# 605_motor2.net
KiCad netlist of a schematic drawn in EAGLE
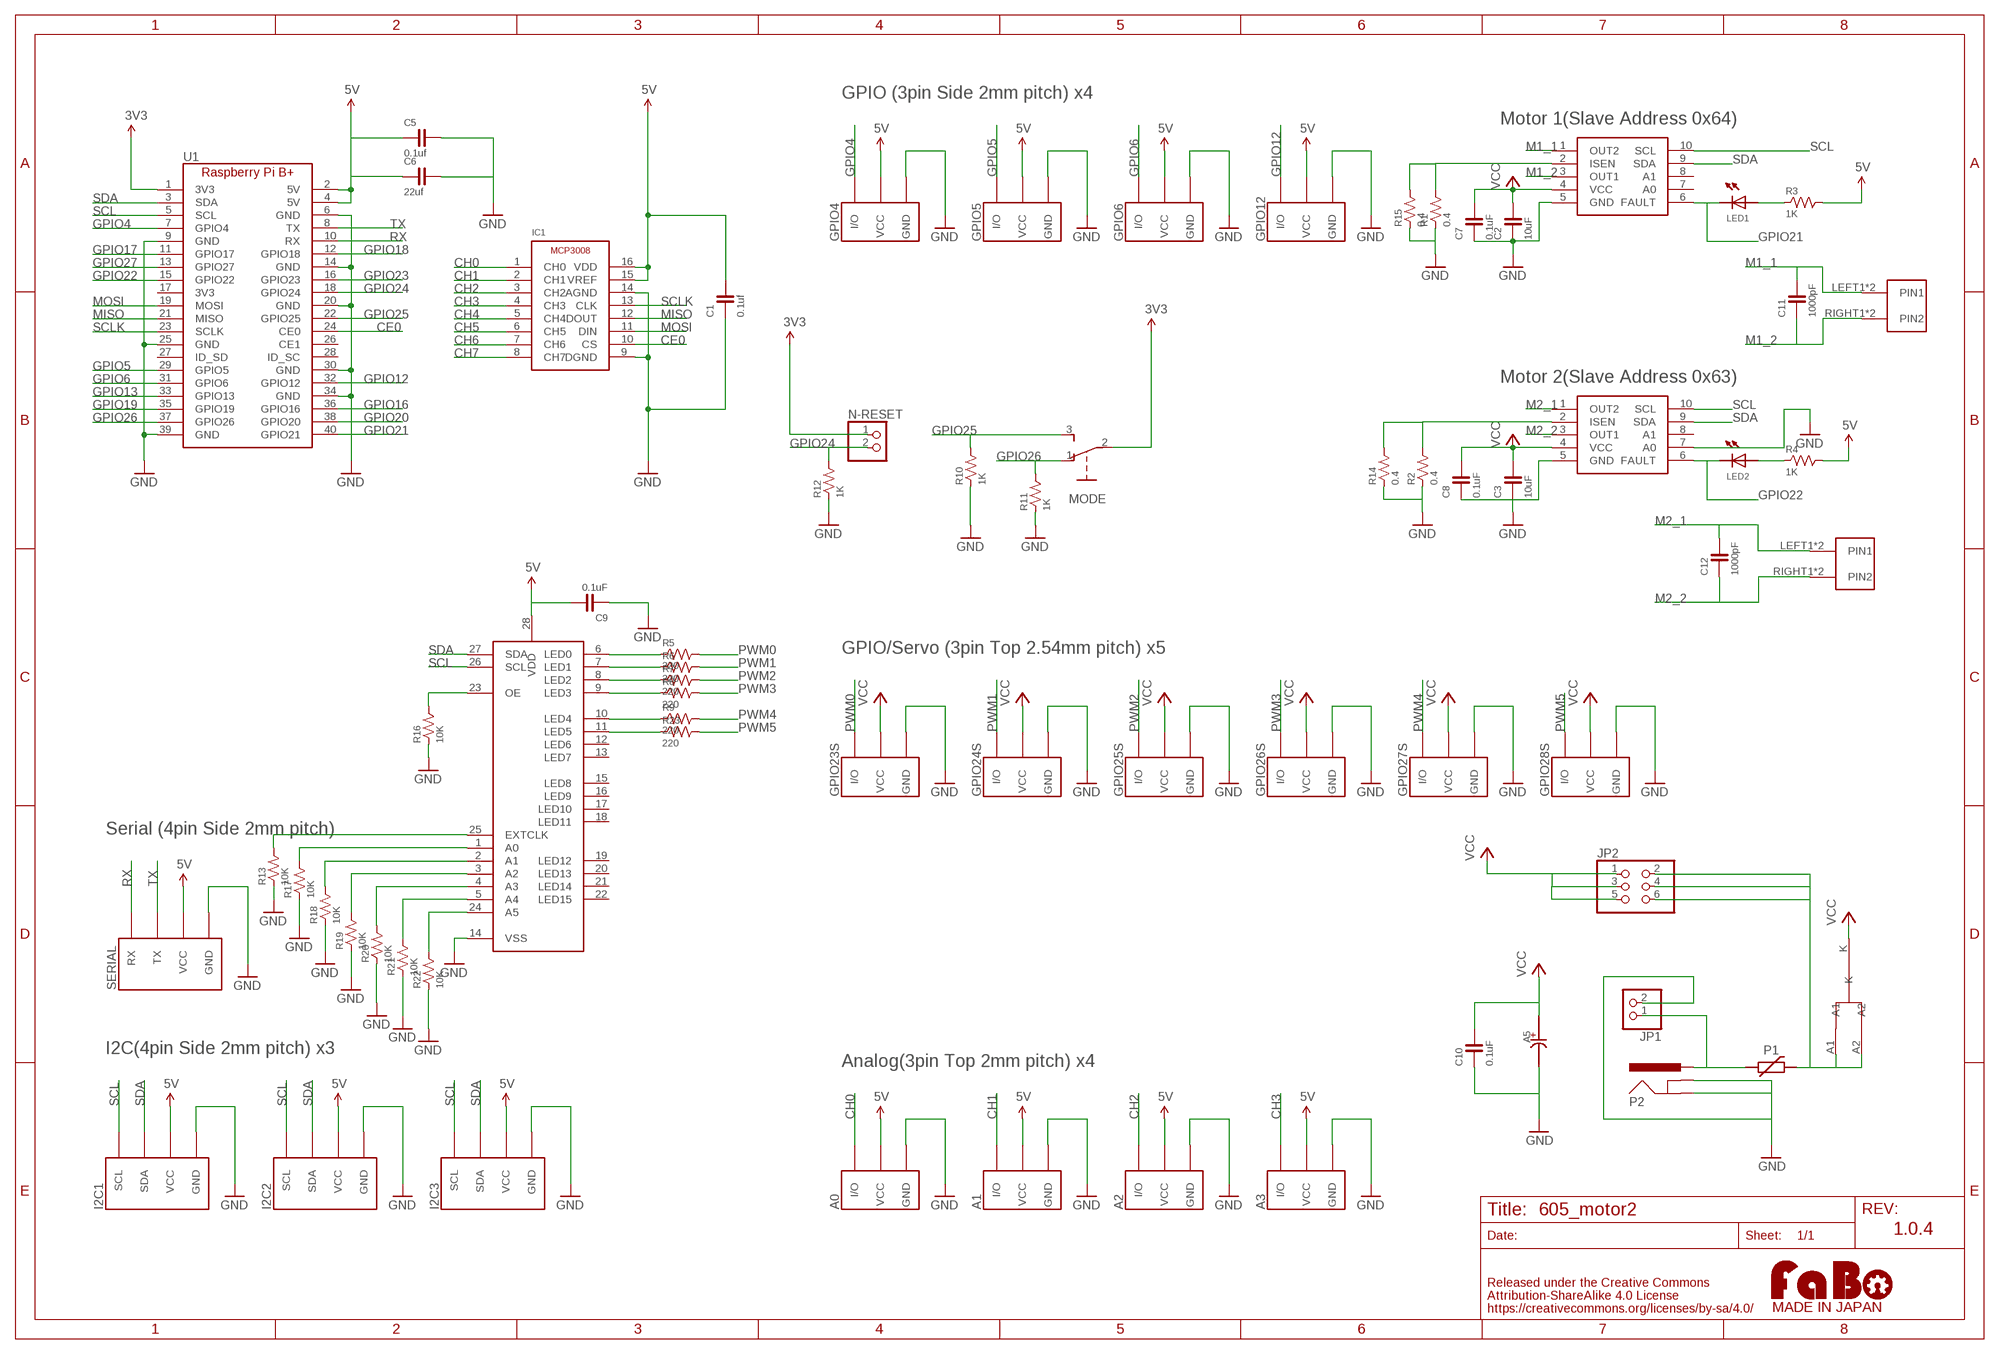
[diagram p0: schematic, sheet 1]

(export (version "E")
  (design (tool "Eeschema 10.0.6"))
  (components
    (comp (ref "A0")
      (value "FABO_BRICK_3PIN-B03B-PASK-1")
      (footprint "eagle-import:FABO_BRICK_3PIN_B03B-PASK-1")
      (libsource (lib "eagle-import") (part "FABO_BRICK_3PIN-B03B-PASK-1"))
    )
    (comp (ref "A1")
      (value "FABO_BRICK_3PIN-B03B-PASK-1")
      (footprint "eagle-import:FABO_BRICK_3PIN_B03B-PASK-1")
      (libsource (lib "eagle-import") (part "FABO_BRICK_3PIN-B03B-PASK-1"))
    )
    (comp (ref "A2")
      (value "FABO_BRICK_3PIN-B03B-PASK-1")
      (footprint "eagle-import:FABO_BRICK_3PIN_B03B-PASK-1")
      (libsource (lib "eagle-import") (part "FABO_BRICK_3PIN-B03B-PASK-1"))
    )
    (comp (ref "A3")
      (value "FABO_BRICK_3PIN-B03B-PASK-1")
      (footprint "eagle-import:FABO_BRICK_3PIN_B03B-PASK-1")
      (libsource (lib "eagle-import") (part "FABO_BRICK_3PIN-B03B-PASK-1"))
    )
    (comp (ref "A5")
      (value "CAPACITOR-ALUMIN_D12_5")
      (footprint "eagle-import:D12.5")
      (libsource (lib "eagle-import") (part "CAPACITOR-ALUMIN_D12_5"))
    )
    (comp (ref "C1")
      (value "0.1uf")
      (footprint "eagle-import:0603")
      (libsource (lib "eagle-import") (part "CAPACITOR-0603"))
    )
    (comp (ref "C2")
      (value "10uF")
      (footprint "eagle-import:0603")
      (libsource (lib "eagle-import") (part "CAPACITOR-0603"))
    )
    (comp (ref "C3")
      (value "10uF")
      (footprint "eagle-import:0603")
      (libsource (lib "eagle-import") (part "CAPACITOR-0603"))
    )
    (comp (ref "C5")
      (value "0.1uf")
      (footprint "eagle-import:0603")
      (libsource (lib "eagle-import") (part "CAPACITOR-0603"))
    )
    (comp (ref "C6")
      (value "22uf")
      (footprint "eagle-import:0603")
      (libsource (lib "eagle-import") (part "CAPACITOR-0603"))
    )
    (comp (ref "C7")
      (value "0.1uF")
      (footprint "eagle-import:0603")
      (libsource (lib "eagle-import") (part "CAPACITOR-0603"))
    )
    (comp (ref "C8")
      (value "0.1uF")
      (footprint "eagle-import:0603")
      (libsource (lib "eagle-import") (part "CAPACITOR-0603"))
    )
    (comp (ref "C9")
      (value "0.1uF")
      (footprint "eagle-import:0603")
      (libsource (lib "eagle-import") (part "CAPACITOR-0603"))
    )
    (comp (ref "C10")
      (value "0.1uF")
      (footprint "eagle-import:0603")
      (libsource (lib "eagle-import") (part "CAPACITOR-0603"))
    )
    (comp (ref "C11")
      (value "1000pF")
      (footprint "eagle-import:0603")
      (libsource (lib "eagle-import") (part "CAPACITOR-0603"))
    )
    (comp (ref "C12")
      (value "1000pF")
      (footprint "eagle-import:0603")
      (libsource (lib "eagle-import") (part "CAPACITOR-0603"))
    )
    (comp (ref "GPIO4")
      (value "FABO_BRICK_3PIN-S03B-PASK-2")
      (footprint "eagle-import:FABO_BRICK_3PIN_S03B-PASK-2")
      (libsource (lib "eagle-import") (part "FABO_BRICK_3PIN-S03B-PASK-2"))
    )
    (comp (ref "GPIO5")
      (value "FABO_BRICK_3PIN-S03B-PASK-2")
      (footprint "eagle-import:FABO_BRICK_3PIN_S03B-PASK-2")
      (libsource (lib "eagle-import") (part "FABO_BRICK_3PIN-S03B-PASK-2"))
    )
    (comp (ref "GPIO6")
      (value "FABO_BRICK_3PIN-S03B-PASK-2")
      (footprint "eagle-import:FABO_BRICK_3PIN_S03B-PASK-2")
      (libsource (lib "eagle-import") (part "FABO_BRICK_3PIN-S03B-PASK-2"))
    )
    (comp (ref "GPIO12")
      (value "FABO_BRICK_3PIN-S03B-PASK-2")
      (footprint "eagle-import:FABO_BRICK_3PIN_S03B-PASK-2")
      (libsource (lib "eagle-import") (part "FABO_BRICK_3PIN-S03B-PASK-2"))
    )
    (comp (ref "GPIO23S")
      (value "FABO_BRICK_3PIN-HEADER")
      (footprint "eagle-import:FABO_BRICK_3PIN_HEADER")
      (libsource (lib "eagle-import") (part "FABO_BRICK_3PIN-HEADER"))
    )
    (comp (ref "GPIO24S")
      (value "FABO_BRICK_3PIN-HEADER")
      (footprint "eagle-import:FABO_BRICK_3PIN_HEADER")
      (libsource (lib "eagle-import") (part "FABO_BRICK_3PIN-HEADER"))
    )
    (comp (ref "GPIO25S")
      (value "FABO_BRICK_3PIN-HEADER")
      (footprint "eagle-import:FABO_BRICK_3PIN_HEADER")
      (libsource (lib "eagle-import") (part "FABO_BRICK_3PIN-HEADER"))
    )
    (comp (ref "GPIO26S")
      (value "FABO_BRICK_3PIN-HEADER")
      (footprint "eagle-import:FABO_BRICK_3PIN_HEADER")
      (libsource (lib "eagle-import") (part "FABO_BRICK_3PIN-HEADER"))
    )
    (comp (ref "GPIO27S")
      (value "FABO_BRICK_3PIN-HEADER")
      (footprint "eagle-import:FABO_BRICK_3PIN_HEADER")
      (libsource (lib "eagle-import") (part "FABO_BRICK_3PIN-HEADER"))
    )
    (comp (ref "GPIO28S")
      (value "FABO_BRICK_3PIN-HEADER")
      (footprint "eagle-import:FABO_BRICK_3PIN_HEADER")
      (libsource (lib "eagle-import") (part "FABO_BRICK_3PIN-HEADER"))
    )
    (comp (ref "I2C1")
      (value "FABO_BRICK_I2C-S04B-PASK-2")
      (footprint "eagle-import:FABO_BRICK_I2C_S04B-PASK-2")
      (libsource (lib "eagle-import") (part "FABO_BRICK_I2C-S04B-PASK-2"))
    )
    (comp (ref "I2C2")
      (value "FABO_BRICK_I2C-S04B-PASK-2")
      (footprint "eagle-import:FABO_BRICK_I2C_S04B-PASK-2")
      (libsource (lib "eagle-import") (part "FABO_BRICK_I2C-S04B-PASK-2"))
    )
    (comp (ref "I2C3")
      (value "FABO_BRICK_I2C-S04B-PASK-2")
      (footprint "eagle-import:FABO_BRICK_I2C_S04B-PASK-2")
      (libsource (lib "eagle-import") (part "FABO_BRICK_I2C-S04B-PASK-2"))
    )
    (comp (ref "IC1")
      (value "MICROCHIP-MCP3008")
      (footprint "eagle-import:MICROCHIP-MCP3008")
      (libsource (lib "eagle-import") (part "MICROCHIP-MCP3008"))
    )
    (comp (ref "JP1")
      (value "PINHD-1X2")
      (footprint "eagle-import:1X02")
      (libsource (lib "eagle-import") (part "PINHD-1X2"))
    )
    (comp (ref "JP2")
      (value "PINHD-2X3")
      (footprint "eagle-import:2X03")
      (libsource (lib "eagle-import") (part "PINHD-2X3"))
    )
    (comp (ref "LED1")
      (value "LED-0603")
      (footprint "eagle-import:0603")
      (libsource (lib "eagle-import") (part "LED-0603"))
    )
    (comp (ref "LED2")
      (value "LED-0603")
      (footprint "eagle-import:0603")
      (libsource (lib "eagle-import") (part "LED-0603"))
    )
    (comp (ref "MODE")
      (value "SLIDE-EG1218")
      (footprint "eagle-import:EG1218")
      (libsource (lib "eagle-import") (part "SLIDE-EG1218"))
    )
    (comp (ref "N-RESET")
      (value "PINHD-1X2")
      (footprint "eagle-import:1X02")
      (libsource (lib "eagle-import") (part "PINHD-1X2"))
    )
    (comp (ref "P1")
      (value "POLYSWITCH1206")
      (footprint "eagle-import:1206")
      (libsource (lib "eagle-import") (part "POLYSWITCH1206"))
    )
    (comp (ref "P2")
      (value "DC-JACKM04339A0")
      (footprint "eagle-import:M04339A0")
      (libsource (lib "eagle-import") (part "DC-JACKM04339A0"))
    )
    (comp (ref "R1")
      (value "0.4")
      (footprint "eagle-import:0603")
      (libsource (lib "eagle-import") (part "RESISTOR-0603"))
    )
    (comp (ref "R2")
      (value "0.4")
      (footprint "eagle-import:0603")
      (libsource (lib "eagle-import") (part "RESISTOR-0603"))
    )
    (comp (ref "R3")
      (value "1K")
      (footprint "eagle-import:0603")
      (libsource (lib "eagle-import") (part "RESISTOR-0603"))
    )
    (comp (ref "R4")
      (value "1K")
      (footprint "eagle-import:0603")
      (libsource (lib "eagle-import") (part "RESISTOR-0603"))
    )
    (comp (ref "R5")
      (value "220")
      (footprint "eagle-import:0603")
      (libsource (lib "eagle-import") (part "RESISTOR-0603"))
    )
    (comp (ref "R6")
      (value "220")
      (footprint "eagle-import:0603")
      (libsource (lib "eagle-import") (part "RESISTOR-0603"))
    )
    (comp (ref "R7")
      (value "220")
      (footprint "eagle-import:0603")
      (libsource (lib "eagle-import") (part "RESISTOR-0603"))
    )
    (comp (ref "R8")
      (value "220")
      (footprint "eagle-import:0603")
      (libsource (lib "eagle-import") (part "RESISTOR-0603"))
    )
    (comp (ref "R9")
      (value "220")
      (footprint "eagle-import:0603")
      (libsource (lib "eagle-import") (part "RESISTOR-0603"))
    )
    (comp (ref "R10")
      (value "1K")
      (footprint "eagle-import:0603")
      (libsource (lib "eagle-import") (part "RESISTOR-0603"))
    )
    (comp (ref "R11")
      (value "1K")
      (footprint "eagle-import:0603")
      (libsource (lib "eagle-import") (part "RESISTOR-0603"))
    )
    (comp (ref "R12")
      (value "1K")
      (footprint "eagle-import:0603")
      (libsource (lib "eagle-import") (part "RESISTOR-0603"))
    )
    (comp (ref "R13")
      (value "10K")
      (footprint "eagle-import:0402")
      (libsource (lib "eagle-import") (part "RESISTOR-0402"))
    )
    (comp (ref "R14")
      (value "0.4")
      (footprint "eagle-import:0603")
      (libsource (lib "eagle-import") (part "RESISTOR-0603"))
    )
    (comp (ref "R15")
      (value "0.4")
      (footprint "eagle-import:0603")
      (libsource (lib "eagle-import") (part "RESISTOR-0603"))
    )
    (comp (ref "R16")
      (value "10K")
      (footprint "eagle-import:0603")
      (libsource (lib "eagle-import") (part "RESISTOR-0603"))
    )
    (comp (ref "R17")
      (value "10K")
      (footprint "eagle-import:0603")
      (libsource (lib "eagle-import") (part "RESISTOR-0603"))
    )
    (comp (ref "R18")
      (value "10K")
      (footprint "eagle-import:0603")
      (libsource (lib "eagle-import") (part "RESISTOR-0603"))
    )
    (comp (ref "R19")
      (value "10K")
      (footprint "eagle-import:0603")
      (libsource (lib "eagle-import") (part "RESISTOR-0603"))
    )
    (comp (ref "R20")
      (value "10K")
      (footprint "eagle-import:0603")
      (libsource (lib "eagle-import") (part "RESISTOR-0603"))
    )
    (comp (ref "R21")
      (value "10K")
      (footprint "eagle-import:0603")
      (libsource (lib "eagle-import") (part "RESISTOR-0603"))
    )
    (comp (ref "R22")
      (value "10K")
      (footprint "eagle-import:0402")
      (libsource (lib "eagle-import") (part "RESISTOR-0402"))
    )
    (comp (ref "R23")
      (value "220")
      (footprint "eagle-import:0603")
      (libsource (lib "eagle-import") (part "RESISTOR-0603"))
    )
    (comp (ref "S1")
      (value "STPS15L30C")
      (footprint "eagle-import:STPS15L30C")
      (libsource (lib "eagle-import") (part "STPS15L30C"))
    )
    (comp (ref "SERIAL")
      (value "FABO_BRICK_SERIAL-S04B-PASK-2")
      (footprint "eagle-import:FABO_BRICK_SERIAL_S04B-PASK-2")
      (libsource (lib "eagle-import") (part "FABO_BRICK_SERIAL-S04B-PASK-2"))
    )
    (comp (ref "U$8")
      (value "DRV8830")
      (footprint "eagle-import:DRV8830")
      (libsource (lib "eagle-import") (part "DRV8830"))
    )
    (comp (ref "U$9")
      (value "PCA9685")
      (footprint "eagle-import:PCA9685")
      (libsource (lib "eagle-import") (part "PCA9685"))
    )
    (comp (ref "U$10")
      (value "DRV8830")
      (footprint "eagle-import:DRV8830")
      (libsource (lib "eagle-import") (part "DRV8830"))
    )
    (comp (ref "U$12")
      (value "ML-1400-S1")
      (footprint "eagle-import:ML-1400-S1")
      (libsource (lib "eagle-import") (part "ML-1400-S1"))
    )
    (comp (ref "U$13")
      (value "ML-1400-S1")
      (footprint "eagle-import:ML-1400-S1")
      (libsource (lib "eagle-import") (part "ML-1400-S1"))
    )
    (comp (ref "U$14")
      (value "LOGO_FABO-M")
      (footprint "eagle-import:LOGO_FABO_MS")
      (libsource (lib "eagle-import") (part "LOGO_FABO-M"))
    )
    (comp (ref "U1")
      (value "RASPBERRY_PI_B+")
      (footprint "eagle-import:RASPBERRY_PI_B+")
      (libsource (lib "eagle-import") (part "RASPBERRY_PI_B+"))
    )
  )
  (nets
    (net (code "1") (name "/CE0") (class "Default")
      (node (ref "IC1") (pin "10") (pinfunction "CS_10") (pintype "bidirectional"))
      (node (ref "U1") (pin "24") (pinfunction "CE0_24") (pintype "bidirectional"))
    )
    (net (code "2") (name "/CH0") (class "Default")
      (node (ref "A0") (pin "I/O") (pinfunction "I/O_I/O") (pintype "bidirectional"))
      (node (ref "IC1") (pin "1") (pinfunction "CH0_1") (pintype "bidirectional"))
    )
    (net (code "3") (name "/CH1") (class "Default")
      (node (ref "A1") (pin "I/O") (pinfunction "I/O_I/O") (pintype "bidirectional"))
      (node (ref "IC1") (pin "2") (pinfunction "CH1_2") (pintype "bidirectional"))
    )
    (net (code "4") (name "/CH2") (class "Default")
      (node (ref "A2") (pin "I/O") (pinfunction "I/O_I/O") (pintype "bidirectional"))
      (node (ref "IC1") (pin "3") (pinfunction "CH2_3") (pintype "bidirectional"))
    )
    (net (code "5") (name "/CH3") (class "Default")
      (node (ref "A3") (pin "I/O") (pinfunction "I/O_I/O") (pintype "bidirectional"))
      (node (ref "IC1") (pin "4") (pinfunction "CH3_4") (pintype "bidirectional"))
    )
    (net (code "6") (name "/CH4") (class "Default")
      (node (ref "IC1") (pin "5") (pinfunction "CH4_5") (pintype "bidirectional"))
    )
    (net (code "7") (name "/CH5") (class "Default")
      (node (ref "IC1") (pin "6") (pinfunction "CH5_6") (pintype "bidirectional"))
    )
    (net (code "8") (name "/CH6") (class "Default")
      (node (ref "IC1") (pin "7") (pinfunction "CH6_7") (pintype "bidirectional"))
    )
    (net (code "9") (name "/CH7") (class "Default")
      (node (ref "IC1") (pin "8") (pinfunction "CH7_8") (pintype "bidirectional"))
    )
    (net (code "10") (name "/GPIO4") (class "Default")
      (node (ref "GPIO4") (pin "I/O") (pinfunction "I/O_I/O") (pintype "bidirectional"))
      (node (ref "U1") (pin "7") (pinfunction "GPIO4_7") (pintype "bidirectional"))
    )
    (net (code "11") (name "/GPIO5") (class "Default")
      (node (ref "GPIO5") (pin "I/O") (pinfunction "I/O_I/O") (pintype "bidirectional"))
      (node (ref "U1") (pin "29") (pinfunction "GPIO5_29") (pintype "bidirectional"))
    )
    (net (code "12") (name "/GPIO6") (class "Default")
      (node (ref "GPIO6") (pin "I/O") (pinfunction "I/O_I/O") (pintype "bidirectional"))
      (node (ref "U1") (pin "31") (pinfunction "GPIO6_31") (pintype "bidirectional"))
    )
    (net (code "13") (name "/GPIO12") (class "Default")
      (node (ref "GPIO12") (pin "I/O") (pinfunction "I/O_I/O") (pintype "bidirectional"))
      (node (ref "U1") (pin "32") (pinfunction "GPIO12_32") (pintype "bidirectional"))
    )
    (net (code "14") (name "/GPIO13") (class "Default")
      (node (ref "U1") (pin "33") (pinfunction "GPIO13_33") (pintype "bidirectional"))
    )
    (net (code "15") (name "/GPIO16") (class "Default")
      (node (ref "U1") (pin "36") (pinfunction "GPIO16_36") (pintype "bidirectional"))
    )
    (net (code "16") (name "/GPIO17") (class "Default")
      (node (ref "U1") (pin "11") (pinfunction "GPIO17_11") (pintype "bidirectional"))
    )
    (net (code "17") (name "/GPIO18") (class "Default")
      (node (ref "U1") (pin "12") (pinfunction "GPIO18_12") (pintype "bidirectional"))
    )
    (net (code "18") (name "/GPIO19") (class "Default")
      (node (ref "U1") (pin "35") (pinfunction "GPIO19_35") (pintype "bidirectional"))
    )
    (net (code "19") (name "/GPIO20") (class "Default")
      (node (ref "U1") (pin "38") (pinfunction "GPIO20_38") (pintype "bidirectional"))
    )
    (net (code "20") (name "/GPIO21") (class "Default")
      (node (ref "LED1") (pin "CATHODE") (pinfunction "CATHODE_CATHODE") (pintype "passive"))
      (node (ref "U$8") (pin "6") (pinfunction "FAULT_6") (pintype "bidirectional"))
      (node (ref "U1") (pin "40") (pinfunction "GPIO21_40") (pintype "bidirectional"))
    )
    (net (code "21") (name "/GPIO22") (class "Default")
      (node (ref "LED2") (pin "CATHODE") (pinfunction "CATHODE_CATHODE") (pintype "passive"))
      (node (ref "U$10") (pin "6") (pinfunction "FAULT_6") (pintype "bidirectional"))
      (node (ref "U1") (pin "15") (pinfunction "GPIO22_15") (pintype "bidirectional"))
    )
    (net (code "22") (name "/GPIO23") (class "Default")
      (node (ref "U1") (pin "16") (pinfunction "GPIO23_16") (pintype "bidirectional"))
    )
    (net (code "23") (name "/GPIO24") (class "Default")
      (node (ref "N-RESET") (pin "2") (pinfunction "2_2") (pintype "passive"))
      (node (ref "R12") (pin "2") (pinfunction "2_2") (pintype "bidirectional"))
      (node (ref "U1") (pin "18") (pinfunction "GPIO24_18") (pintype "bidirectional"))
    )
    (net (code "24") (name "/GPIO25") (class "Default")
      (node (ref "MODE") (pin "3") (pinfunction "3_3") (pintype "passive"))
      (node (ref "R10") (pin "2") (pinfunction "2_2") (pintype "bidirectional"))
      (node (ref "U1") (pin "22") (pinfunction "GPIO25_22") (pintype "bidirectional"))
    )
    (net (code "25") (name "/GPIO26") (class "Default")
      (node (ref "MODE") (pin "1") (pinfunction "1_1") (pintype "passive"))
      (node (ref "R11") (pin "2") (pinfunction "2_2") (pintype "bidirectional"))
      (node (ref "U1") (pin "37") (pinfunction "GPIO26_37") (pintype "bidirectional"))
    )
    (net (code "26") (name "/GPIO27") (class "Default")
      (node (ref "U1") (pin "13") (pinfunction "GPIO27_13") (pintype "bidirectional"))
    )
    (net (code "27") (name "/M1_1") (class "Default")
      (node (ref "C11") (pin "2") (pinfunction "2_2") (pintype "passive"))
      (node (ref "U$12") (pin "LEFT1") (pinfunction "PIN1_LEFT1") (pintype "bidirectional"))
      (node (ref "U$12") (pin "LEFT2") (pinfunction "PIN1_LEFT2") (pintype "bidirectional"))
      (node (ref "U$8") (pin "1") (pinfunction "OUT2_1") (pintype "bidirectional"))
    )
    (net (code "28") (name "/M1_2") (class "Default")
      (node (ref "C11") (pin "1") (pinfunction "1_1") (pintype "passive"))
      (node (ref "U$12") (pin "RIGHT1") (pinfunction "PIN2_RIGHT1") (pintype "bidirectional"))
      (node (ref "U$12") (pin "RIGHT2") (pinfunction "PIN2_RIGHT2") (pintype "bidirectional"))
      (node (ref "U$8") (pin "3") (pinfunction "OUT1_3") (pintype "bidirectional"))
    )
    (net (code "29") (name "/M2_1") (class "Default")
      (node (ref "C12") (pin "2") (pinfunction "2_2") (pintype "passive"))
      (node (ref "U$10") (pin "1") (pinfunction "OUT2_1") (pintype "bidirectional"))
      (node (ref "U$13") (pin "LEFT1") (pinfunction "PIN1_LEFT1") (pintype "bidirectional"))
      (node (ref "U$13") (pin "LEFT2") (pinfunction "PIN1_LEFT2") (pintype "bidirectional"))
    )
    (net (code "30") (name "/M2_2") (class "Default")
      (node (ref "C12") (pin "1") (pinfunction "1_1") (pintype "passive"))
      (node (ref "U$10") (pin "3") (pinfunction "OUT1_3") (pintype "bidirectional"))
      (node (ref "U$13") (pin "RIGHT1") (pinfunction "PIN2_RIGHT1") (pintype "bidirectional"))
      (node (ref "U$13") (pin "RIGHT2") (pinfunction "PIN2_RIGHT2") (pintype "bidirectional"))
    )
    (net (code "31") (name "/MISO") (class "Default")
      (node (ref "IC1") (pin "12") (pinfunction "DOUT_12") (pintype "bidirectional"))
      (node (ref "U1") (pin "21") (pinfunction "MISO_21") (pintype "bidirectional"))
    )
    (net (code "32") (name "/MOSI") (class "Default")
      (node (ref "IC1") (pin "11") (pinfunction "DIN_11") (pintype "bidirectional"))
      (node (ref "U1") (pin "19") (pinfunction "MOSI_19") (pintype "bidirectional"))
    )
    (net (code "33") (name "/PWM0") (class "Default")
      (node (ref "GPIO23S") (pin "I/O") (pinfunction "I/O_I/O") (pintype "bidirectional"))
      (node (ref "R5") (pin "2") (pinfunction "2_2") (pintype "bidirectional"))
    )
    (net (code "34") (name "/PWM1") (class "Default")
      (node (ref "GPIO24S") (pin "I/O") (pinfunction "I/O_I/O") (pintype "bidirectional"))
      (node (ref "R6") (pin "2") (pinfunction "2_2") (pintype "bidirectional"))
    )
    (net (code "35") (name "/PWM2") (class "Default")
      (node (ref "GPIO25S") (pin "I/O") (pinfunction "I/O_I/O") (pintype "bidirectional"))
      (node (ref "R7") (pin "2") (pinfunction "2_2") (pintype "bidirectional"))
    )
    (net (code "36") (name "/PWM3") (class "Default")
      (node (ref "GPIO26S") (pin "I/O") (pinfunction "I/O_I/O") (pintype "bidirectional"))
      (node (ref "R8") (pin "2") (pinfunction "2_2") (pintype "bidirectional"))
    )
    (net (code "37") (name "/PWM4") (class "Default")
      (node (ref "GPIO27S") (pin "I/O") (pinfunction "I/O_I/O") (pintype "bidirectional"))
      (node (ref "R9") (pin "2") (pinfunction "2_2") (pintype "bidirectional"))
    )
    (net (code "38") (name "/PWM5") (class "Default")
      (node (ref "GPIO28S") (pin "I/O") (pinfunction "I/O_I/O") (pintype "bidirectional"))
      (node (ref "R23") (pin "2") (pinfunction "2_2") (pintype "bidirectional"))
    )
    (net (code "39") (name "/RX") (class "Default")
      (node (ref "SERIAL") (pin "RX") (pinfunction "RX_RX") (pintype "bidirectional"))
      (node (ref "U1") (pin "10") (pinfunction "RX_10") (pintype "bidirectional"))
    )
    (net (code "40") (name "/SCL") (class "Default")
      (node (ref "I2C1") (pin "SCL") (pinfunction "SCL_SCL") (pintype "bidirectional"))
      (node (ref "I2C2") (pin "SCL") (pinfunction "SCL_SCL") (pintype "bidirectional"))
      (node (ref "I2C3") (pin "SCL") (pinfunction "SCL_SCL") (pintype "bidirectional"))
      (node (ref "U$10") (pin "10") (pinfunction "SCL_10") (pintype "bidirectional"))
      (node (ref "U$8") (pin "10") (pinfunction "SCL_10") (pintype "bidirectional"))
      (node (ref "U$9") (pin "26") (pinfunction "SCL_26") (pintype "bidirectional"))
      (node (ref "U1") (pin "5") (pinfunction "SCL_5") (pintype "bidirectional"))
    )
    (net (code "41") (name "/SCLK") (class "Default")
      (node (ref "IC1") (pin "13") (pinfunction "CLK_13") (pintype "bidirectional"))
      (node (ref "U1") (pin "23") (pinfunction "SCLK_23") (pintype "bidirectional"))
    )
    (net (code "42") (name "/SDA") (class "Default")
      (node (ref "I2C1") (pin "SDA") (pinfunction "SDA_SDA") (pintype "bidirectional"))
      (node (ref "I2C2") (pin "SDA") (pinfunction "SDA_SDA") (pintype "bidirectional"))
      (node (ref "I2C3") (pin "SDA") (pinfunction "SDA_SDA") (pintype "bidirectional"))
      (node (ref "U$10") (pin "9") (pinfunction "SDA_9") (pintype "bidirectional"))
      (node (ref "U$8") (pin "9") (pinfunction "SDA_9") (pintype "bidirectional"))
      (node (ref "U$9") (pin "27") (pinfunction "SDA_27") (pintype "bidirectional"))
      (node (ref "U1") (pin "3") (pinfunction "SDA_3") (pintype "bidirectional"))
    )
    (net (code "43") (name "/TX") (class "Default")
      (node (ref "SERIAL") (pin "TX") (pinfunction "TX_TX") (pintype "bidirectional"))
      (node (ref "U1") (pin "8") (pinfunction "TX_8") (pintype "bidirectional"))
    )
    (net (code "44") (name "3V3") (class "Default")
      (node (ref "MODE") (pin "2") (pinfunction "2_2") (pintype "passive"))
      (node (ref "N-RESET") (pin "1") (pinfunction "1_1") (pintype "passive"))
      (node (ref "U1") (pin "1") (pinfunction "3V3_1") (pintype "bidirectional"))
    )
    (net (code "45") (name "5V") (class "Default")
      (node (ref "A0") (pin "VCC") (pinfunction "VCC_VCC") (pintype "bidirectional"))
      (node (ref "A1") (pin "VCC") (pinfunction "VCC_VCC") (pintype "bidirectional"))
      (node (ref "A2") (pin "VCC") (pinfunction "VCC_VCC") (pintype "bidirectional"))
      (node (ref "A3") (pin "VCC") (pinfunction "VCC_VCC") (pintype "bidirectional"))
      (node (ref "C1") (pin "2") (pinfunction "2_2") (pintype "passive"))
      (node (ref "C5") (pin "1") (pinfunction "1_1") (pintype "passive"))
      (node (ref "C6") (pin "1") (pinfunction "1_1") (pintype "passive"))
      (node (ref "C9") (pin "2") (pinfunction "2_2") (pintype "passive"))
      (node (ref "GPIO12") (pin "VCC") (pinfunction "VCC_VCC") (pintype "bidirectional"))
      (node (ref "GPIO4") (pin "VCC") (pinfunction "VCC_VCC") (pintype "bidirectional"))
      (node (ref "GPIO5") (pin "VCC") (pinfunction "VCC_VCC") (pintype "bidirectional"))
      (node (ref "GPIO6") (pin "VCC") (pinfunction "VCC_VCC") (pintype "bidirectional"))
      (node (ref "I2C1") (pin "VCC") (pinfunction "VCC_VCC") (pintype "bidirectional"))
      (node (ref "I2C2") (pin "VCC") (pinfunction "VCC_VCC") (pintype "bidirectional"))
      (node (ref "I2C3") (pin "VCC") (pinfunction "VCC_VCC") (pintype "bidirectional"))
      (node (ref "IC1") (pin "15") (pinfunction "VREF_15") (pintype "bidirectional"))
      (node (ref "IC1") (pin "16") (pinfunction "VDD_16") (pintype "bidirectional"))
      (node (ref "R3") (pin "2") (pinfunction "2_2") (pintype "bidirectional"))
      (node (ref "R4") (pin "2") (pinfunction "2_2") (pintype "bidirectional"))
      (node (ref "SERIAL") (pin "VCC") (pinfunction "VCC_VCC") (pintype "bidirectional"))
      (node (ref "U$9") (pin "28") (pinfunction "VDD_28") (pintype "bidirectional"))
      (node (ref "U1") (pin "2") (pinfunction "5V_2") (pintype "bidirectional"))
      (node (ref "U1") (pin "4") (pinfunction "5V_4") (pintype "bidirectional"))
    )
    (net (code "46") (name "GND") (class "Default")
      (node (ref "A0") (pin "GND") (pinfunction "GND_GND") (pintype "bidirectional"))
      (node (ref "A1") (pin "GND") (pinfunction "GND_GND") (pintype "bidirectional"))
      (node (ref "A2") (pin "GND") (pinfunction "GND_GND") (pintype "bidirectional"))
      (node (ref "A3") (pin "GND") (pinfunction "GND_GND") (pintype "bidirectional"))
      (node (ref "A5") (pin "-") (pinfunction "-_-") (pintype "passive"))
      (node (ref "C1") (pin "1") (pinfunction "1_1") (pintype "passive"))
      (node (ref "C10") (pin "1") (pinfunction "1_1") (pintype "passive"))
      (node (ref "C2") (pin "1") (pinfunction "1_1") (pintype "passive"))
      (node (ref "C3") (pin "1") (pinfunction "1_1") (pintype "passive"))
      (node (ref "C5") (pin "2") (pinfunction "2_2") (pintype "passive"))
      (node (ref "C6") (pin "2") (pinfunction "2_2") (pintype "passive"))
      (node (ref "C7") (pin "1") (pinfunction "1_1") (pintype "passive"))
      (node (ref "C8") (pin "1") (pinfunction "1_1") (pintype "passive"))
      (node (ref "C9") (pin "1") (pinfunction "1_1") (pintype "passive"))
      (node (ref "GPIO12") (pin "GND") (pinfunction "GND_GND") (pintype "bidirectional"))
      (node (ref "GPIO23S") (pin "GND") (pinfunction "GND_GND") (pintype "bidirectional"))
      (node (ref "GPIO24S") (pin "GND") (pinfunction "GND_GND") (pintype "bidirectional"))
      (node (ref "GPIO25S") (pin "GND") (pinfunction "GND_GND") (pintype "bidirectional"))
      (node (ref "GPIO26S") (pin "GND") (pinfunction "GND_GND") (pintype "bidirectional"))
      (node (ref "GPIO27S") (pin "GND") (pinfunction "GND_GND") (pintype "bidirectional"))
      (node (ref "GPIO28S") (pin "GND") (pinfunction "GND_GND") (pintype "bidirectional"))
      (node (ref "GPIO4") (pin "GND") (pinfunction "GND_GND") (pintype "bidirectional"))
      (node (ref "GPIO5") (pin "GND") (pinfunction "GND_GND") (pintype "bidirectional"))
      (node (ref "GPIO6") (pin "GND") (pinfunction "GND_GND") (pintype "bidirectional"))
      (node (ref "I2C1") (pin "GND") (pinfunction "GND_GND") (pintype "bidirectional"))
      (node (ref "I2C2") (pin "GND") (pinfunction "GND_GND") (pintype "bidirectional"))
      (node (ref "I2C3") (pin "GND") (pinfunction "GND_GND") (pintype "bidirectional"))
      (node (ref "IC1") (pin "14") (pinfunction "AGND_14") (pintype "bidirectional"))
      (node (ref "IC1") (pin "9") (pinfunction "DGND_9") (pintype "bidirectional"))
      (node (ref "JP1") (pin "2") (pinfunction "2_2") (pintype "passive"))
      (node (ref "P2") (pin "GND@2") (pinfunction "GND_GND@2") (pintype "bidirectional"))
      (node (ref "P2") (pin "GND@3") (pinfunction "GNDBREAK_GND@3") (pintype "bidirectional"))
      (node (ref "R1") (pin "1") (pinfunction "1_1") (pintype "bidirectional"))
      (node (ref "R10") (pin "1") (pinfunction "1_1") (pintype "bidirectional"))
      (node (ref "R11") (pin "1") (pinfunction "1_1") (pintype "bidirectional"))
      (node (ref "R12") (pin "1") (pinfunction "1_1") (pintype "bidirectional"))
      (node (ref "R13") (pin "P$1") (pinfunction "1_P$1") (pintype "bidirectional"))
      (node (ref "R14") (pin "1") (pinfunction "1_1") (pintype "bidirectional"))
      (node (ref "R15") (pin "1") (pinfunction "1_1") (pintype "bidirectional"))
      (node (ref "R16") (pin "1") (pinfunction "1_1") (pintype "bidirectional"))
      (node (ref "R17") (pin "1") (pinfunction "1_1") (pintype "bidirectional"))
      (node (ref "R18") (pin "1") (pinfunction "1_1") (pintype "bidirectional"))
      (node (ref "R19") (pin "1") (pinfunction "1_1") (pintype "bidirectional"))
      (node (ref "R2") (pin "1") (pinfunction "1_1") (pintype "bidirectional"))
      (node (ref "R20") (pin "1") (pinfunction "1_1") (pintype "bidirectional"))
      (node (ref "R21") (pin "1") (pinfunction "1_1") (pintype "bidirectional"))
      (node (ref "R22") (pin "P$1") (pinfunction "1_P$1") (pintype "bidirectional"))
      (node (ref "SERIAL") (pin "GND") (pinfunction "GND_GND") (pintype "bidirectional"))
      (node (ref "U$10") (pin "5") (pinfunction "GND_5") (pintype "bidirectional"))
      (node (ref "U$10") (pin "7") (pinfunction "A0_7") (pintype "bidirectional"))
      (node (ref "U$8") (pin "5") (pinfunction "GND_5") (pintype "bidirectional"))
      (node (ref "U$9") (pin "14") (pinfunction "VSS_14") (pintype "bidirectional"))
      (node (ref "U1") (pin "14") (pinfunction "GND_14") (pintype "bidirectional"))
      (node (ref "U1") (pin "20") (pinfunction "GND_20") (pintype "bidirectional"))
      (node (ref "U1") (pin "25") (pinfunction "GND_25") (pintype "bidirectional"))
      (node (ref "U1") (pin "30") (pinfunction "GND_30") (pintype "bidirectional"))
      (node (ref "U1") (pin "34") (pinfunction "GND_34") (pintype "bidirectional"))
      (node (ref "U1") (pin "39") (pinfunction "GND_39") (pintype "bidirectional"))
      (node (ref "U1") (pin "6") (pinfunction "GND_6") (pintype "bidirectional"))
      (node (ref "U1") (pin "9") (pinfunction "GND_9") (pintype "bidirectional"))
    )
    (net (code "47") (name "Net-(LED1-PadANODE)") (class "Default")
      (node (ref "LED1") (pin "ANODE") (pinfunction "ANODE_ANODE") (pintype "passive"))
      (node (ref "R3") (pin "1") (pinfunction "1_1") (pintype "bidirectional"))
    )
    (net (code "48") (name "Net-(LED2-PadANODE)") (class "Default")
      (node (ref "LED2") (pin "ANODE") (pinfunction "ANODE_ANODE") (pintype "passive"))
      (node (ref "R4") (pin "1") (pinfunction "1_1") (pintype "bidirectional"))
    )
    (net (code "49") (name "Net-(P1-1)") (class "Default")
      (node (ref "JP1") (pin "1") (pinfunction "1_1") (pintype "passive"))
      (node (ref "P1") (pin "P$1") (pinfunction "1_P$1") (pintype "bidirectional"))
      (node (ref "P2") (pin "VCC") (pinfunction "PWR_VCC") (pintype "bidirectional"))
    )
    (net (code "50") (name "Net-(P1-2)") (class "Default")
      (node (ref "JP2") (pin "2") (pinfunction "2_2") (pintype "passive"))
      (node (ref "JP2") (pin "4") (pinfunction "4_4") (pintype "passive"))
      (node (ref "JP2") (pin "6") (pinfunction "6_6") (pintype "passive"))
      (node (ref "P1") (pin "P$2") (pinfunction "2_P$2") (pintype "bidirectional"))
      (node (ref "S1") (pin "A1") (pinfunction "A1_A1") (pintype "bidirectional"))
      (node (ref "S1") (pin "A2") (pinfunction "A2_A2") (pintype "bidirectional"))
    )
    (net (code "51") (name "Net-(R13-2)") (class "Default")
      (node (ref "R13") (pin "P$2") (pinfunction "2_P$2") (pintype "bidirectional"))
      (node (ref "U$9") (pin "25") (pinfunction "EXTCLK_25") (pintype "bidirectional"))
    )
    (net (code "52") (name "Net-(R22-2)") (class "Default")
      (node (ref "R22") (pin "P$2") (pinfunction "2_P$2") (pintype "bidirectional"))
      (node (ref "U$9") (pin "24") (pinfunction "A5_24") (pintype "bidirectional"))
    )
    (net (code "53") (name "Net-(U$8-ISEN)") (class "Default")
      (node (ref "R1") (pin "2") (pinfunction "2_2") (pintype "bidirectional"))
      (node (ref "R15") (pin "2") (pinfunction "2_2") (pintype "bidirectional"))
      (node (ref "U$8") (pin "2") (pinfunction "ISEN_2") (pintype "bidirectional"))
    )
    (net (code "54") (name "Net-(U$9-A0)") (class "Default")
      (node (ref "R17") (pin "2") (pinfunction "2_2") (pintype "bidirectional"))
      (node (ref "U$9") (pin "1") (pinfunction "A0_1") (pintype "bidirectional"))
    )
    (net (code "55") (name "Net-(U$9-A1)") (class "Default")
      (node (ref "R18") (pin "2") (pinfunction "2_2") (pintype "bidirectional"))
      (node (ref "U$9") (pin "2") (pinfunction "A1_2") (pintype "bidirectional"))
    )
    (net (code "56") (name "Net-(U$9-A2)") (class "Default")
      (node (ref "R19") (pin "2") (pinfunction "2_2") (pintype "bidirectional"))
      (node (ref "U$9") (pin "3") (pinfunction "A2_3") (pintype "bidirectional"))
    )
    (net (code "57") (name "Net-(U$9-A3)") (class "Default")
      (node (ref "R20") (pin "2") (pinfunction "2_2") (pintype "bidirectional"))
      (node (ref "U$9") (pin "4") (pinfunction "A3_4") (pintype "bidirectional"))
    )
    (net (code "58") (name "Net-(U$9-A4)") (class "Default")
      (node (ref "R21") (pin "2") (pinfunction "2_2") (pintype "bidirectional"))
      (node (ref "U$9") (pin "5") (pinfunction "A4_5") (pintype "bidirectional"))
    )
    (net (code "59") (name "Net-(U$9-LED0)") (class "Default")
      (node (ref "R5") (pin "1") (pinfunction "1_1") (pintype "bidirectional"))
      (node (ref "U$9") (pin "6") (pinfunction "LED0_6") (pintype "bidirectional"))
    )
    (net (code "60") (name "Net-(U$9-LED1)") (class "Default")
      (node (ref "R6") (pin "1") (pinfunction "1_1") (pintype "bidirectional"))
      (node (ref "U$9") (pin "7") (pinfunction "LED1_7") (pintype "bidirectional"))
    )
    (net (code "61") (name "Net-(U$9-LED2)") (class "Default")
      (node (ref "R7") (pin "1") (pinfunction "1_1") (pintype "bidirectional"))
      (node (ref "U$9") (pin "8") (pinfunction "LED2_8") (pintype "bidirectional"))
    )
    (net (code "62") (name "Net-(U$9-LED3)") (class "Default")
      (node (ref "R8") (pin "1") (pinfunction "1_1") (pintype "bidirectional"))
      (node (ref "U$9") (pin "9") (pinfunction "LED3_9") (pintype "bidirectional"))
    )
    (net (code "63") (name "Net-(U$9-LED4)") (class "Default")
      (node (ref "R9") (pin "1") (pinfunction "1_1") (pintype "bidirectional"))
      (node (ref "U$9") (pin "10") (pinfunction "LED4_10") (pintype "bidirectional"))
    )
    (net (code "64") (name "Net-(U$9-LED5)") (class "Default")
      (node (ref "R23") (pin "1") (pinfunction "1_1") (pintype "bidirectional"))
      (node (ref "U$9") (pin "11") (pinfunction "LED5_11") (pintype "bidirectional"))
    )
    (net (code "65") (name "Net-(U$9-OE)") (class "Default")
      (node (ref "R16") (pin "2") (pinfunction "2_2") (pintype "bidirectional"))
      (node (ref "U$9") (pin "23") (pinfunction "OE_23") (pintype "bidirectional"))
    )
    (net (code "66") (name "Net-(U$10-ISEN)") (class "Default")
      (node (ref "R14") (pin "2") (pinfunction "2_2") (pintype "bidirectional"))
      (node (ref "R2") (pin "2") (pinfunction "2_2") (pintype "bidirectional"))
      (node (ref "U$10") (pin "2") (pinfunction "ISEN_2") (pintype "bidirectional"))
    )
    (net (code "67") (name "VCC") (class "Default")
      (node (ref "A5") (pin "+") (pinfunction "+_+") (pintype "passive"))
      (node (ref "C10") (pin "2") (pinfunction "2_2") (pintype "passive"))
      (node (ref "C2") (pin "2") (pinfunction "2_2") (pintype "passive"))
      (node (ref "C3") (pin "2") (pinfunction "2_2") (pintype "passive"))
      (node (ref "C7") (pin "2") (pinfunction "2_2") (pintype "passive"))
      (node (ref "C8") (pin "2") (pinfunction "2_2") (pintype "passive"))
      (node (ref "GPIO23S") (pin "VCC") (pinfunction "VCC_VCC") (pintype "bidirectional"))
      (node (ref "GPIO24S") (pin "VCC") (pinfunction "VCC_VCC") (pintype "bidirectional"))
      (node (ref "GPIO25S") (pin "VCC") (pinfunction "VCC_VCC") (pintype "bidirectional"))
      (node (ref "GPIO26S") (pin "VCC") (pinfunction "VCC_VCC") (pintype "bidirectional"))
      (node (ref "GPIO27S") (pin "VCC") (pinfunction "VCC_VCC") (pintype "bidirectional"))
      (node (ref "GPIO28S") (pin "VCC") (pinfunction "VCC_VCC") (pintype "bidirectional"))
      (node (ref "JP2") (pin "1") (pinfunction "1_1") (pintype "passive"))
      (node (ref "JP2") (pin "3") (pinfunction "3_3") (pintype "passive"))
      (node (ref "JP2") (pin "5") (pinfunction "5_5") (pintype "passive"))
      (node (ref "S1") (pin "K") (pinfunction "K_K") (pintype "bidirectional"))
      (node (ref "U$10") (pin "4") (pinfunction "VCC_4") (pintype "bidirectional"))
      (node (ref "U$8") (pin "4") (pinfunction "VCC_4") (pintype "bidirectional"))
    )
    (net (code "68") (name "unconnected-(U$8-A0-Pad7)") (class "Default")
      (node (ref "U$8") (pin "7") (pinfunction "A0_7") (pintype "bidirectional"))
    )
    (net (code "69") (name "unconnected-(U$8-A1-Pad8)") (class "Default")
      (node (ref "U$8") (pin "8") (pinfunction "A1_8") (pintype "bidirectional"))
    )
    (net (code "70") (name "unconnected-(U$9-LED6-Pad12)") (class "Default")
      (node (ref "U$9") (pin "12") (pinfunction "LED6_12") (pintype "bidirectional"))
    )
    (net (code "71") (name "unconnected-(U$9-LED7-Pad13)") (class "Default")
      (node (ref "U$9") (pin "13") (pinfunction "LED7_13") (pintype "bidirectional"))
    )
    (net (code "72") (name "unconnected-(U$9-LED8-Pad15)") (class "Default")
      (node (ref "U$9") (pin "15") (pinfunction "LED8_15") (pintype "bidirectional"))
    )
    (net (code "73") (name "unconnected-(U$9-LED9-Pad16)") (class "Default")
      (node (ref "U$9") (pin "16") (pinfunction "LED9_16") (pintype "bidirectional"))
    )
    (net (code "74") (name "unconnected-(U$9-LED10-Pad17)") (class "Default")
      (node (ref "U$9") (pin "17") (pinfunction "LED10_17") (pintype "bidirectional"))
    )
    (net (code "75") (name "unconnected-(U$9-LED11-Pad18)") (class "Default")
      (node (ref "U$9") (pin "18") (pinfunction "LED11_18") (pintype "bidirectional"))
    )
    (net (code "76") (name "unconnected-(U$9-LED12-Pad19)") (class "Default")
      (node (ref "U$9") (pin "19") (pinfunction "LED12_19") (pintype "bidirectional"))
    )
    (net (code "77") (name "unconnected-(U$9-LED13-Pad20)") (class "Default")
      (node (ref "U$9") (pin "20") (pinfunction "LED13_20") (pintype "bidirectional"))
    )
    (net (code "78") (name "unconnected-(U$9-LED14-Pad21)") (class "Default")
      (node (ref "U$9") (pin "21") (pinfunction "LED14_21") (pintype "bidirectional"))
    )
    (net (code "79") (name "unconnected-(U$9-LED15-Pad22)") (class "Default")
      (node (ref "U$9") (pin "22") (pinfunction "LED15_22") (pintype "bidirectional"))
    )
    (net (code "80") (name "unconnected-(U$10-A1-Pad8)") (class "Default")
      (node (ref "U$10") (pin "8") (pinfunction "A1_8") (pintype "bidirectional"))
    )
    (net (code "81") (name "unconnected-(U1-3V3-Pad17)") (class "Default")
      (node (ref "U1") (pin "17") (pinfunction "3V3_17") (pintype "bidirectional"))
    )
    (net (code "82") (name "unconnected-(U1-CE1-Pad26)") (class "Default")
      (node (ref "U1") (pin "26") (pinfunction "CE1_26") (pintype "bidirectional"))
    )
    (net (code "83") (name "unconnected-(U1-ID_SC-Pad28)") (class "Default")
      (node (ref "U1") (pin "28") (pinfunction "ID_SC_28") (pintype "bidirectional"))
    )
    (net (code "84") (name "unconnected-(U1-ID_SD-Pad27)") (class "Default")
      (node (ref "U1") (pin "27") (pinfunction "ID_SD_27") (pintype "bidirectional"))
    )
  )
)
